# WCH_hairDrierCore_V1_5.net
KiCad netlist of a schematic drawn in Altium Designer
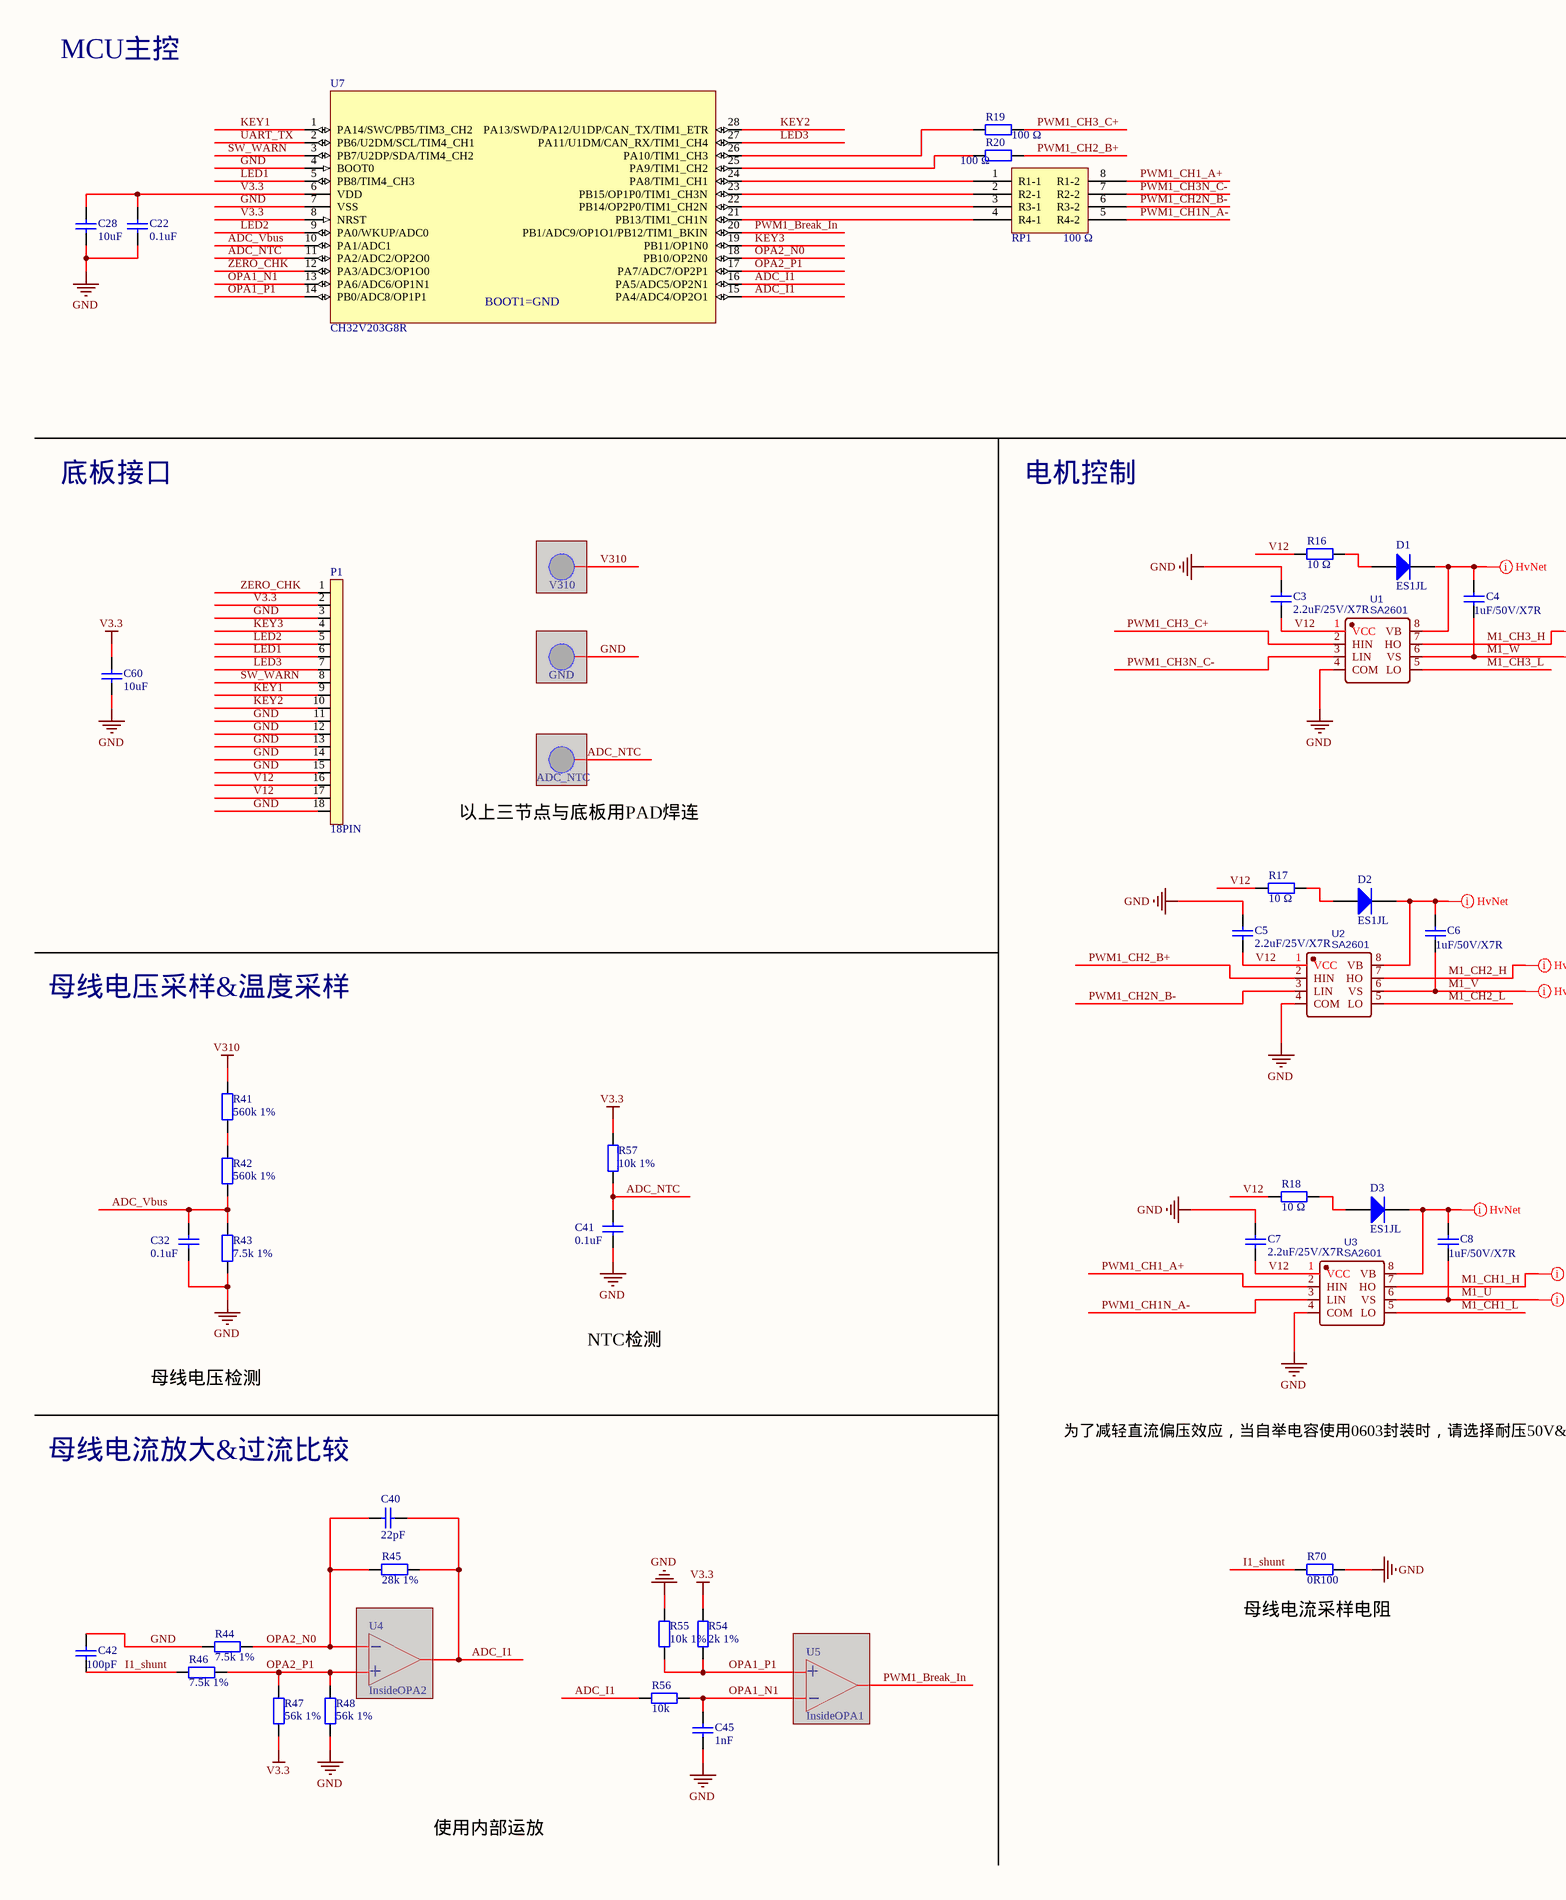
[diagram p0: WCH_hairDrierCore_V1.5.SchDoc, left]
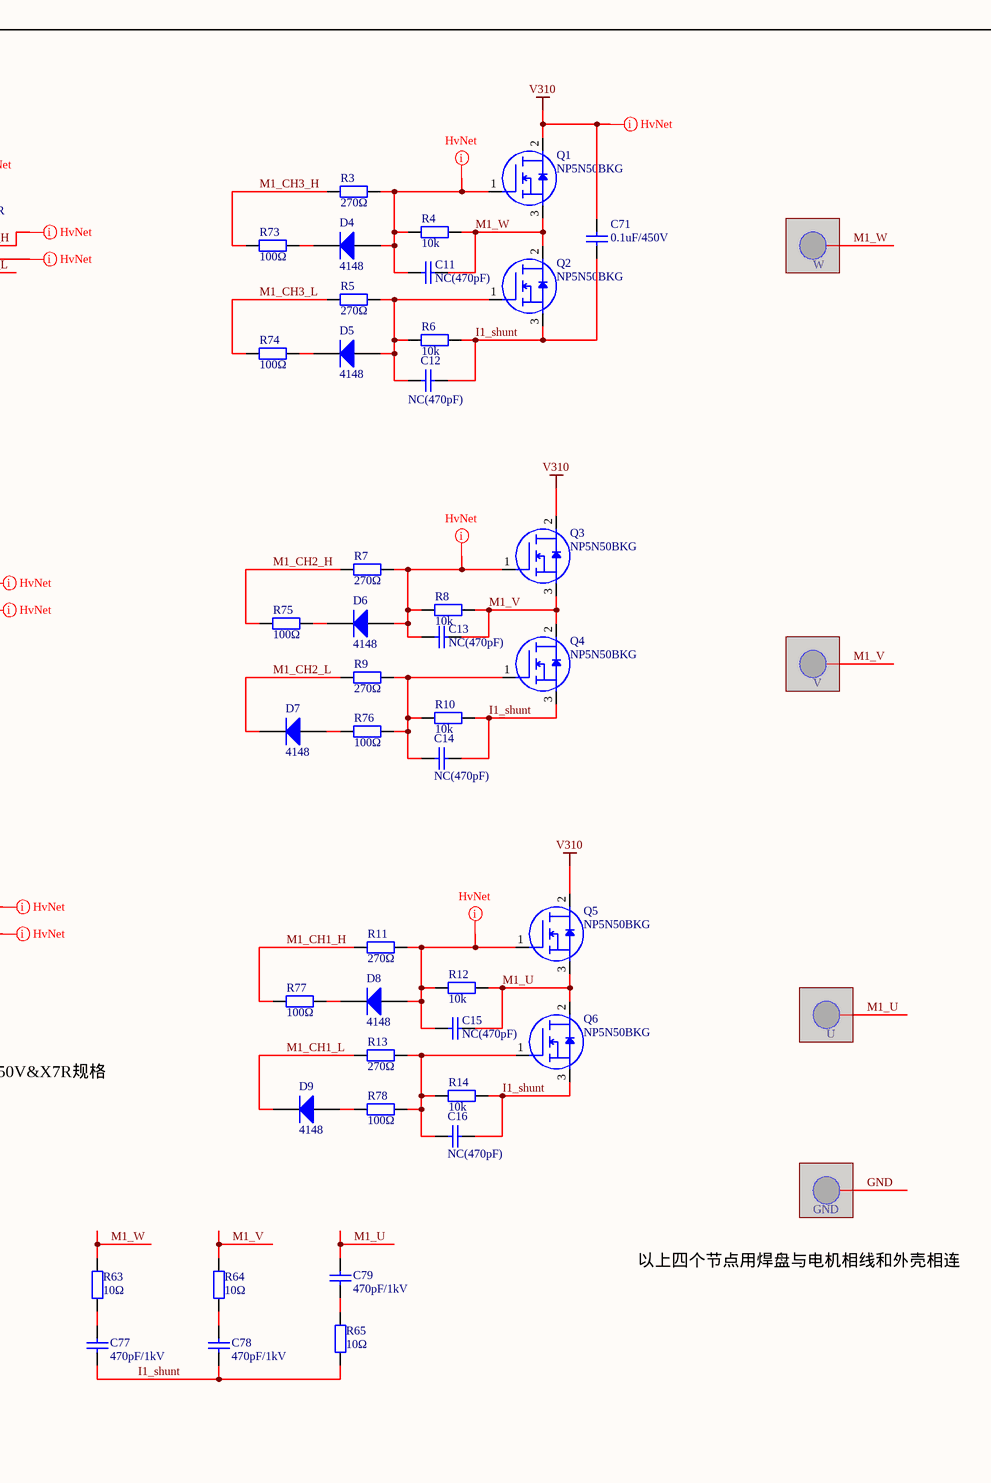
[diagram p1: WCH_hairDrierCore_V1.5.SchDoc, right]

(export (version "E")
  (design (tool "Eeschema 10.0.6"))
  (components
    (comp (ref "C3")
      (value "2.2uF/25V/X7R")
      (footprint "M_C0805")
      (description "Capacitor (Semiconductor SIM Model)")
      (fields (field (name "PUBLISHER") "Altium Limited"))
      (libsource (lib "Miscellaneous Devices") (part "Cap Semi"))
    )
    (comp (ref "C4")
      (value "1uF/50V/X7R")
      (footprint "M_C0805")
      (description "Capacitor (Semiconductor SIM Model)")
      (fields (field (name "PUBLISHER") "Altium Limited"))
      (libsource (lib "Miscellaneous Devices") (part "Cap Semi"))
    )
    (comp (ref "C5")
      (value "2.2uF/25V/X7R")
      (footprint "M_C0805")
      (description "Capacitor (Semiconductor SIM Model)")
      (fields (field (name "PUBLISHER") "Altium Limited"))
      (libsource (lib "Miscellaneous Devices") (part "Cap Semi"))
    )
    (comp (ref "C6")
      (value "1uF/50V/X7R")
      (footprint "M_C0805")
      (description "Capacitor (Semiconductor SIM Model)")
      (fields (field (name "PUBLISHER") "Altium Limited"))
      (libsource (lib "Miscellaneous Devices") (part "Cap Semi"))
    )
    (comp (ref "C7")
      (value "2.2uF/25V/X7R")
      (footprint "M_C0805")
      (description "Capacitor (Semiconductor SIM Model)")
      (fields (field (name "PUBLISHER") "Altium Limited"))
      (libsource (lib "Miscellaneous Devices") (part "Cap Semi"))
    )
    (comp (ref "C8")
      (value "1uF/50V/X7R")
      (footprint "M_C0805")
      (description "Capacitor (Semiconductor SIM Model)")
      (fields (field (name "PUBLISHER") "Altium Limited"))
      (libsource (lib "Miscellaneous Devices") (part "Cap Semi"))
    )
    (comp (ref "C11")
      (value "NC(470pF)")
      (footprint "M_C0402-")
      (description "Capacitor (Semiconductor SIM Model)")
      (fields (field (name "PUBLISHER") "Altium Limited"))
      (libsource (lib "Miscellaneous Devices") (part "Cap Semi"))
    )
    (comp (ref "C12")
      (value "NC(470pF)")
      (footprint "M_C0402-")
      (description "Capacitor (Semiconductor SIM Model)")
      (fields (field (name "PUBLISHER") "Altium Limited"))
      (libsource (lib "Miscellaneous Devices") (part "Cap Semi"))
    )
    (comp (ref "C13")
      (value "NC(470pF)")
      (footprint "M_C0402-")
      (description "Capacitor (Semiconductor SIM Model)")
      (fields (field (name "PUBLISHER") "Altium Limited"))
      (libsource (lib "Miscellaneous Devices") (part "Cap Semi"))
    )
    (comp (ref "C14")
      (value "NC(470pF)")
      (footprint "M_C0402-")
      (description "Capacitor (Semiconductor SIM Model)")
      (fields (field (name "PUBLISHER") "Altium Limited"))
      (libsource (lib "Miscellaneous Devices") (part "Cap Semi"))
    )
    (comp (ref "C15")
      (value "NC(470pF)")
      (footprint "M_C0402-")
      (description "Capacitor (Semiconductor SIM Model)")
      (fields (field (name "PUBLISHER") "Altium Limited"))
      (libsource (lib "Miscellaneous Devices") (part "Cap Semi"))
    )
    (comp (ref "C16")
      (value "NC(470pF)")
      (footprint "M_C0402-")
      (description "Capacitor (Semiconductor SIM Model)")
      (fields (field (name "PUBLISHER") "Altium Limited"))
      (libsource (lib "Miscellaneous Devices") (part "Cap Semi"))
    )
    (comp (ref "C22")
      (value "0.1uF")
      (footprint "C0402S")
      (description "Capacitor (Semiconductor SIM Model)")
      (fields (field (name "PUBLISHER") "Altium Limited"))
      (libsource (lib "Miscellaneous Devices") (part "Cap Semi"))
    )
    (comp (ref "C28")
      (value "10uF")
      (footprint "0603C")
      (description "Capacitor (Semiconductor SIM Model)")
      (fields (field (name "PUBLISHER") "Altium Limited"))
      (libsource (lib "Miscellaneous Devices") (part "Cap Semi"))
    )
    (comp (ref "C32")
      (value "0.1uF")
      (footprint "C0402S")
      (description "Capacitor (Semiconductor SIM Model)")
      (fields (field (name "PUBLISHER") "Altium Limited"))
      (libsource (lib "Miscellaneous Devices") (part "Cap Semi"))
    )
    (comp (ref "C40")
      (value "22pF")
      (footprint "C0402S")
      (description "Capacitor (Semiconductor SIM Model)")
      (fields (field (name "PUBLISHER") "Altium Limited"))
      (libsource (lib "Miscellaneous Devices") (part "Cap Semi"))
    )
    (comp (ref "C41")
      (value "0.1uF")
      (footprint "C0402S")
      (description "Capacitor (Semiconductor SIM Model)")
      (fields (field (name "PUBLISHER") "Altium Limited"))
      (libsource (lib "Miscellaneous Devices") (part "Cap Semi"))
    )
    (comp (ref "C42")
      (value "100pF")
      (footprint "C0402S")
      (description "Capacitor (Semiconductor SIM Model)")
      (fields (field (name "PUBLISHER") "Altium Limited"))
      (libsource (lib "Miscellaneous Devices") (part "Cap Semi"))
    )
    (comp (ref "C45")
      (value "1nF")
      (footprint "C0402S")
      (description "Capacitor (Semiconductor SIM Model)")
      (fields (field (name "PUBLISHER") "Altium Limited"))
      (libsource (lib "Miscellaneous Devices") (part "Cap Semi"))
    )
    (comp (ref "C60")
      (value "10uF")
      (footprint "0603C")
      (description "Capacitor (Semiconductor SIM Model)")
      (fields (field (name "PUBLISHER") "Altium Limited"))
      (libsource (lib "Miscellaneous Devices") (part "Cap Semi"))
    )
    (comp (ref "C71")
      (value "0.1uF/450V")
      (footprint "1206-")
      (description "Capacitor (Semiconductor SIM Model)")
      (fields (field (name "PUBLISHER") "Altium Limited"))
      (libsource (lib "Miscellaneous Devices") (part "Cap Semi"))
    )
    (comp (ref "C77")
      (value "470pF/1kV")
      (footprint "M_C1206-")
      (description "Capacitor (Semiconductor SIM Model)")
      (fields (field (name "PUBLISHER") "Altium Limited"))
      (libsource (lib "Miscellaneous Devices") (part "Cap Semi"))
    )
    (comp (ref "C78")
      (value "470pF/1kV")
      (footprint "M_C1206-")
      (description "Capacitor (Semiconductor SIM Model)")
      (fields (field (name "PUBLISHER") "Altium Limited"))
      (libsource (lib "Miscellaneous Devices") (part "Cap Semi"))
    )
    (comp (ref "C79")
      (value "470pF/1kV")
      (footprint "M_C1206-")
      (description "Capacitor (Semiconductor SIM Model)")
      (fields (field (name "PUBLISHER") "Altium Limited"))
      (libsource (lib "Miscellaneous Devices") (part "Cap Semi"))
    )
    (comp (ref "D1")
      (value "ES1JL")
      (footprint "SOD-123")
      (description "High Conductance Fast Diode")
      (fields (field (name "PUBLISHER") "Altium Limited"))
      (libsource (lib "Miscellaneous Devices") (part "Diode 1N4148"))
    )
    (comp (ref "D2")
      (value "ES1JL")
      (footprint "SOD-123")
      (description "High Conductance Fast Diode")
      (fields (field (name "PUBLISHER") "Altium Limited"))
      (libsource (lib "Miscellaneous Devices") (part "Diode 1N4148"))
    )
    (comp (ref "D3")
      (value "ES1JL")
      (footprint "SOD-123")
      (description "High Conductance Fast Diode")
      (fields (field (name "PUBLISHER") "Altium Limited"))
      (libsource (lib "Miscellaneous Devices") (part "Diode 1N4148"))
    )
    (comp (ref "D4")
      (value "4148")
      (footprint "SOD523")
      (description "High Conductance Fast Diode")
      (fields (field (name "PUBLISHER") "Altium Limited"))
      (libsource (lib "Miscellaneous Devices") (part "Diode 1N4148"))
    )
    (comp (ref "D5")
      (value "4148")
      (footprint "SOD523")
      (description "High Conductance Fast Diode")
      (fields (field (name "PUBLISHER") "Altium Limited"))
      (libsource (lib "Miscellaneous Devices") (part "Diode 1N4148"))
    )
    (comp (ref "D6")
      (value "4148")
      (footprint "SOD523")
      (description "High Conductance Fast Diode")
      (fields (field (name "PUBLISHER") "Altium Limited"))
      (libsource (lib "Miscellaneous Devices") (part "Diode 1N4148"))
    )
    (comp (ref "D7")
      (value "4148")
      (footprint "SOD523")
      (description "High Conductance Fast Diode")
      (fields (field (name "PUBLISHER") "Altium Limited"))
      (libsource (lib "Miscellaneous Devices") (part "Diode 1N4148"))
    )
    (comp (ref "D8")
      (value "4148")
      (footprint "SOD523")
      (description "High Conductance Fast Diode")
      (fields (field (name "PUBLISHER") "Altium Limited"))
      (libsource (lib "Miscellaneous Devices") (part "Diode 1N4148"))
    )
    (comp (ref "D9")
      (value "4148")
      (footprint "SOD523")
      (description "High Conductance Fast Diode")
      (fields (field (name "PUBLISHER") "Altium Limited"))
      (libsource (lib "Miscellaneous Devices") (part "Diode 1N4148"))
    )
    (comp (ref "P1") (value "18PIN") (footprint "P1.27-18-SMD") (libsource (lib "SUNWIN_SCH") (part "18PIN")))
    (comp (ref "Q1")
      (value "NP5N50BKG")
      (footprint "D-PAK-1")
      (libsource (lib "SUNWIN_SCH") (part "MOSFET-N"))
    )
    (comp (ref "Q2")
      (value "NP5N50BKG")
      (footprint "D-PAK-1")
      (libsource (lib "SUNWIN_SCH") (part "MOSFET-N"))
    )
    (comp (ref "Q3")
      (value "NP5N50BKG")
      (footprint "D-PAK-1")
      (libsource (lib "SUNWIN_SCH") (part "MOSFET-N"))
    )
    (comp (ref "Q4")
      (value "NP5N50BKG")
      (footprint "D-PAK-1")
      (libsource (lib "SUNWIN_SCH") (part "MOSFET-N"))
    )
    (comp (ref "Q5")
      (value "NP5N50BKG")
      (footprint "D-PAK-1")
      (libsource (lib "SUNWIN_SCH") (part "MOSFET-N"))
    )
    (comp (ref "Q6")
      (value "NP5N50BKG")
      (footprint "D-PAK-1")
      (libsource (lib "SUNWIN_SCH") (part "MOSFET-N"))
    )
    (comp (ref "R3")
      (value "270Ω")
      (footprint "M_R0402-")
      (description "Resistor")
      (fields (field (name "PUBLISHER") "Altium Limited"))
      (libsource (lib "") (part "Res2_1"))
    )
    (comp (ref "R4")
      (value "10k")
      (footprint "0402S")
      (description "Resistor")
      (fields (field (name "PUBLISHER") "Altium Limited"))
      (libsource (lib "") (part "Res2_1"))
    )
    (comp (ref "R5")
      (value "270Ω")
      (footprint "M_R0402-")
      (description "Resistor")
      (fields (field (name "PUBLISHER") "Altium Limited"))
      (libsource (lib "") (part "Res2_1"))
    )
    (comp (ref "R6")
      (value "10k")
      (footprint "0402S")
      (description "Resistor")
      (fields (field (name "PUBLISHER") "Altium Limited"))
      (libsource (lib "") (part "Res2_1"))
    )
    (comp (ref "R7")
      (value "270Ω")
      (footprint "M_R0402-")
      (description "Resistor")
      (fields (field (name "PUBLISHER") "Altium Limited"))
      (libsource (lib "") (part "Res2_1"))
    )
    (comp (ref "R8")
      (value "10k")
      (footprint "0402S")
      (description "Resistor")
      (fields (field (name "PUBLISHER") "Altium Limited"))
      (libsource (lib "") (part "Res2_1"))
    )
    (comp (ref "R9")
      (value "270Ω")
      (footprint "M_R0402-")
      (description "Resistor")
      (fields (field (name "PUBLISHER") "Altium Limited"))
      (libsource (lib "") (part "Res2_1"))
    )
    (comp (ref "R10")
      (value "10k")
      (footprint "0402S")
      (description "Resistor")
      (fields (field (name "PUBLISHER") "Altium Limited"))
      (libsource (lib "") (part "Res2_1"))
    )
    (comp (ref "R11")
      (value "270Ω")
      (footprint "M_R0402-")
      (description "Resistor")
      (fields (field (name "PUBLISHER") "Altium Limited"))
      (libsource (lib "") (part "Res2_1"))
    )
    (comp (ref "R12")
      (value "10k")
      (footprint "0402S")
      (description "Resistor")
      (fields (field (name "PUBLISHER") "Altium Limited"))
      (libsource (lib "") (part "Res2_1"))
    )
    (comp (ref "R13")
      (value "270Ω")
      (footprint "M_R0402-")
      (description "Resistor")
      (fields (field (name "PUBLISHER") "Altium Limited"))
      (libsource (lib "") (part "Res2_1"))
    )
    (comp (ref "R14")
      (value "10k")
      (footprint "0402S")
      (description "Resistor")
      (fields (field (name "PUBLISHER") "Altium Limited"))
      (libsource (lib "") (part "Res2_1"))
    )
    (comp (ref "R16")
      (value "10 Ω")
      (footprint "0603")
      (description "Resistor")
      (fields (field (name "PUBLISHER") "Altium Limited"))
      (libsource (lib "") (part "Res2_1"))
    )
    (comp (ref "R17")
      (value "10 Ω")
      (footprint "0603")
      (description "Resistor")
      (fields (field (name "PUBLISHER") "Altium Limited"))
      (libsource (lib "") (part "Res2_1"))
    )
    (comp (ref "R18")
      (value "10 Ω")
      (footprint "0603")
      (description "Resistor")
      (fields (field (name "PUBLISHER") "Altium Limited"))
      (libsource (lib "") (part "Res2_1"))
    )
    (comp (ref "R19")
      (value "100 Ω")
      (footprint "C0402S")
      (description "Resistor")
      (fields (field (name "PUBLISHER") "Altium Limited"))
      (libsource (lib "") (part "Res2_1"))
    )
    (comp (ref "R20")
      (value "100 Ω")
      (footprint "C0402S")
      (description "Resistor")
      (fields (field (name "PUBLISHER") "Altium Limited"))
      (libsource (lib "") (part "Res2_1"))
    )
    (comp (ref "R41")
      (value "560k 1%")
      (footprint "1206-")
      (description "Resistor")
      (fields (field (name "PUBLISHER") "Altium Limited"))
      (libsource (lib "Miscellaneous Devices") (part "Res2"))
    )
    (comp (ref "R42")
      (value "560k 1%")
      (footprint "1206-")
      (description "Resistor")
      (fields (field (name "PUBLISHER") "Altium Limited"))
      (libsource (lib "Miscellaneous Devices") (part "Res2"))
    )
    (comp (ref "R43")
      (value "7.5k 1%")
      (footprint "0402S")
      (description "Resistor")
      (fields (field (name "PUBLISHER") "Altium Limited"))
      (libsource (lib "Miscellaneous Devices") (part "Res2"))
    )
    (comp (ref "R44")
      (value "7.5k 1%")
      (footprint "0402S")
      (description "Resistor")
      (fields (field (name "PUBLISHER") "Altium Limited"))
      (libsource (lib "") (part "Res2_2"))
    )
    (comp (ref "R45")
      (value "28k 1%")
      (footprint "0402S")
      (description "Resistor")
      (fields (field (name "PUBLISHER") "Altium Limited"))
      (libsource (lib "") (part "Res2_2"))
    )
    (comp (ref "R46")
      (value "7.5k 1%")
      (footprint "0402S")
      (description "Resistor")
      (fields (field (name "PUBLISHER") "Altium Limited"))
      (libsource (lib "") (part "Res2_2"))
    )
    (comp (ref "R47")
      (value "56k 1%")
      (footprint "0402S")
      (description "Resistor")
      (fields (field (name "PUBLISHER") "Altium Limited"))
      (libsource (lib "Miscellaneous Devices") (part "Res2"))
    )
    (comp (ref "R48")
      (value "56k 1%")
      (footprint "0402S")
      (description "Resistor")
      (fields (field (name "PUBLISHER") "Altium Limited"))
      (libsource (lib "Miscellaneous Devices") (part "Res2"))
    )
    (comp (ref "R54")
      (value "2k 1%")
      (footprint "0402S")
      (description "Resistor")
      (fields (field (name "PUBLISHER") "Altium Limited"))
      (libsource (lib "") (part "Res2_3"))
    )
    (comp (ref "R55")
      (value "10k 1%")
      (footprint "0402S")
      (description "Resistor")
      (fields (field (name "PUBLISHER") "Altium Limited"))
      (libsource (lib "Miscellaneous Devices") (part "Res2"))
    )
    (comp (ref "R56")
      (value "10k")
      (footprint "0402S")
      (description "Resistor")
      (fields (field (name "PUBLISHER") "Altium Limited"))
      (libsource (lib "") (part "Res2_2"))
    )
    (comp (ref "R57")
      (value "10k 1%")
      (footprint "0402S")
      (description "Resistor")
      (fields (field (name "PUBLISHER") "Altium Limited"))
      (libsource (lib "") (part "Res2_3"))
    )
    (comp (ref "R63")
      (value "10Ω")
      (footprint "M_R0805-")
      (description "Resistor")
      (fields (field (name "PUBLISHER") "Altium Limited"))
      (libsource (lib "Miscellaneous Devices") (part "Res2"))
    )
    (comp (ref "R64")
      (value "10Ω")
      (footprint "M_R0805-")
      (description "Resistor")
      (fields (field (name "PUBLISHER") "Altium Limited"))
      (libsource (lib "Miscellaneous Devices") (part "Res2"))
    )
    (comp (ref "R65")
      (value "10Ω")
      (footprint "M_R0805-")
      (description "Resistor")
      (fields (field (name "PUBLISHER") "Altium Limited"))
      (libsource (lib "Miscellaneous Devices") (part "Res2"))
    )
    (comp (ref "R70")
      (value "0R100")
      (footprint "1210")
      (description "Resistor")
      (fields (field (name "PUBLISHER") "Altium Limited"))
      (libsource (lib "") (part "Res2_1"))
    )
    (comp (ref "R73")
      (value "100Ω")
      (footprint "M_R0402-")
      (description "Resistor")
      (fields (field (name "PUBLISHER") "Altium Limited"))
      (libsource (lib "") (part "Res2_1"))
    )
    (comp (ref "R74")
      (value "100Ω")
      (footprint "M_R0402-")
      (description "Resistor")
      (fields (field (name "PUBLISHER") "Altium Limited"))
      (libsource (lib "") (part "Res2_1"))
    )
    (comp (ref "R75")
      (value "100Ω")
      (footprint "M_R0402-")
      (description "Resistor")
      (fields (field (name "PUBLISHER") "Altium Limited"))
      (libsource (lib "") (part "Res2_1"))
    )
    (comp (ref "R76")
      (value "100Ω")
      (footprint "M_R0402-")
      (description "Resistor")
      (fields (field (name "PUBLISHER") "Altium Limited"))
      (libsource (lib "") (part "Res2_1"))
    )
    (comp (ref "R77")
      (value "100Ω")
      (footprint "M_R0402-")
      (description "Resistor")
      (fields (field (name "PUBLISHER") "Altium Limited"))
      (libsource (lib "") (part "Res2_1"))
    )
    (comp (ref "R78")
      (value "100Ω")
      (footprint "M_R0402-")
      (description "Resistor")
      (fields (field (name "PUBLISHER") "Altium Limited"))
      (libsource (lib "") (part "Res2_1"))
    )
    (comp (ref "RP1") (value "100 Ω") (footprint "RP4-0402") (libsource (lib "WJ1") (part "Rp4")))
    (comp (ref "U1")
      (value "SA2601")
      (footprint "SOP8")
      (fields
        (field (name "BOM_SUPPLIER PART") "C537541")
        (field (name "BOM_MANUFACTURER PART") "IR2101SPBF")
        (field (name "CONTRIBUTOR") "LCSC")
      )
      (libsource (lib "altium-import") (part "root_0_IR2101SPBF_"))
    )
    (comp (ref "U2")
      (value "SA2601")
      (footprint "SOP8")
      (fields
        (field (name "BOM_SUPPLIER PART") "C537541")
        (field (name "BOM_MANUFACTURER PART") "IR2101SPBF")
        (field (name "CONTRIBUTOR") "LCSC")
      )
      (libsource (lib "altium-import") (part "root_0_IR2101SPBF_"))
    )
    (comp (ref "U3")
      (value "SA2601")
      (footprint "SOP8")
      (fields
        (field (name "BOM_SUPPLIER PART") "C537541")
        (field (name "BOM_MANUFACTURER PART") "IR2101SPBF")
        (field (name "CONTRIBUTOR") "LCSC")
      )
      (libsource (lib "altium-import") (part "root_0_IR2101SPBF_"))
    )
    (comp (ref "U4") (value "InsideOPA2") (libsource (lib "WJ1") (part "InsideOPA")))
    (comp (ref "U5") (value "InsideOPA1") (libsource (lib "WJ1") (part "InsideOPA2")))
    (comp (ref "U7")
      (value "CH32V203G8R")
      (footprint "QSOP28")
      (description "RISC-V LMD-MCU, 144MHz, for motor & wireless charging")
      (libsource (lib "CHXXX") (part "CH32V203G8R"))
    )
  )
  (nets
    (net (code "1") (name "/ADC_I1") (class "Default")
      (node (ref "C40") (pin "1") (pinfunction "1_1") (pintype "passive"))
      (node (ref "R45") (pin "2") (pinfunction "2_2") (pintype "passive"))
      (node (ref "R56") (pin "1") (pinfunction "1_1") (pintype "passive"))
      (node (ref "U7") (pin "15") (pinfunction "PA4/ADC4/OP2O1_15") (pintype "bidirectional"))
      (node (ref "U7") (pin "16") (pinfunction "PA5/ADC5/OP2N1_16") (pintype "bidirectional"))
    )
    (net (code "2") (name "/ADC_NTC") (class "Default")
      (node (ref "C41") (pin "1") (pinfunction "1_1") (pintype "passive"))
      (node (ref "R57") (pin "2") (pinfunction "2_2") (pintype "passive"))
      (node (ref "U7") (pin "11") (pinfunction "PA2/ADC2/OP2O0_11") (pintype "bidirectional"))
    )
    (net (code "3") (name "/ADC_Vbus") (class "Default")
      (node (ref "C32") (pin "1") (pinfunction "1_1") (pintype "passive"))
      (node (ref "R42") (pin "1") (pinfunction "1_1") (pintype "passive"))
      (node (ref "R43") (pin "2") (pinfunction "2_2") (pintype "passive"))
      (node (ref "U7") (pin "10") (pinfunction "PA1/ADC1_10") (pintype "bidirectional"))
    )
    (net (code "4") (name "/I1_shunt") (class "Default")
      (node (ref "C12") (pin "2") (pinfunction "2_2") (pintype "passive"))
      (node (ref "C14") (pin "2") (pinfunction "2_2") (pintype "passive"))
      (node (ref "C16") (pin "2") (pinfunction "2_2") (pintype "passive"))
      (node (ref "C42") (pin "2") (pinfunction "2_2") (pintype "passive"))
      (node (ref "C71") (pin "2") (pinfunction "2_2") (pintype "passive"))
      (node (ref "C77") (pin "1") (pinfunction "1_1") (pintype "passive"))
      (node (ref "C78") (pin "1") (pinfunction "1_1") (pintype "passive"))
      (node (ref "Q2") (pin "3") (pinfunction "S_3") (pintype "passive"))
      (node (ref "Q4") (pin "3") (pinfunction "S_3") (pintype "passive"))
      (node (ref "Q6") (pin "3") (pinfunction "S_3") (pintype "passive"))
      (node (ref "R10") (pin "1") (pinfunction "1_1") (pintype "passive"))
      (node (ref "R14") (pin "1") (pinfunction "1_1") (pintype "passive"))
      (node (ref "R46") (pin "1") (pinfunction "1_1") (pintype "passive"))
      (node (ref "R6") (pin "1") (pinfunction "1_1") (pintype "passive"))
      (node (ref "R65") (pin "1") (pinfunction "1_1") (pintype "passive"))
      (node (ref "R70") (pin "2") (pinfunction "2_2") (pintype "passive"))
    )
    (net (code "5") (name "/KEY1") (class "Default")
      (node (ref "P1") (pin "9") (pintype "passive"))
      (node (ref "U7") (pin "1") (pinfunction "PA14/SWC/PB5/TIM3_CH2_1") (pintype "bidirectional"))
    )
    (net (code "6") (name "/KEY2") (class "Default")
      (node (ref "P1") (pin "10") (pintype "passive"))
      (node (ref "U7") (pin "28") (pinfunction "PA13/SWD/PA12/U1DP/CAN_TX/TIM1_ETR_28") (pintype "bidirectional"))
    )
    (net (code "7") (name "/KEY3") (class "Default")
      (node (ref "P1") (pin "4") (pintype "passive"))
      (node (ref "U7") (pin "19") (pinfunction "PB11/OP1N0_19") (pintype "bidirectional"))
    )
    (net (code "8") (name "/LED1") (class "Default")
      (node (ref "P1") (pin "6") (pintype "passive"))
      (node (ref "U7") (pin "5") (pinfunction "PB8/TIM4_CH3_5") (pintype "bidirectional"))
    )
    (net (code "9") (name "/LED2") (class "Default")
      (node (ref "P1") (pin "5") (pintype "passive"))
      (node (ref "U7") (pin "9") (pinfunction "PA0/WKUP/ADC0_9") (pintype "bidirectional"))
    )
    (net (code "10") (name "/LED3") (class "Default")
      (node (ref "P1") (pin "7") (pintype "passive"))
      (node (ref "U7") (pin "27") (pinfunction "PA11/U1DM/CAN_RX/TIM1_CH4_27") (pintype "bidirectional"))
    )
    (net (code "11") (name "/M1_CH1_H") (class "Default")
      (node (ref "R11") (pin "2") (pinfunction "2_2") (pintype "passive"))
      (node (ref "R77") (pin "2") (pinfunction "2_2") (pintype "passive"))
      (node (ref "U3") (pin "7") (pinfunction "HO_7") (pintype "passive"))
    )
    (net (code "12") (name "/M1_CH1_L") (class "Default")
      (node (ref "D9") (pin "2") (pinfunction "K_2") (pintype "passive"))
      (node (ref "R13") (pin "2") (pinfunction "2_2") (pintype "passive"))
      (node (ref "U3") (pin "5") (pinfunction "LO_5") (pintype "passive"))
    )
    (net (code "13") (name "/M1_CH2_H") (class "Default")
      (node (ref "R7") (pin "2") (pinfunction "2_2") (pintype "passive"))
      (node (ref "R75") (pin "2") (pinfunction "2_2") (pintype "passive"))
      (node (ref "U2") (pin "7") (pinfunction "HO_7") (pintype "passive"))
    )
    (net (code "14") (name "/M1_CH2_L") (class "Default")
      (node (ref "D7") (pin "2") (pinfunction "K_2") (pintype "passive"))
      (node (ref "R9") (pin "2") (pinfunction "2_2") (pintype "passive"))
      (node (ref "U2") (pin "5") (pinfunction "LO_5") (pintype "passive"))
    )
    (net (code "15") (name "/M1_CH3_H") (class "Default")
      (node (ref "R3") (pin "2") (pinfunction "2_2") (pintype "passive"))
      (node (ref "R73") (pin "2") (pinfunction "2_2") (pintype "passive"))
      (node (ref "U1") (pin "7") (pinfunction "HO_7") (pintype "passive"))
    )
    (net (code "16") (name "/M1_CH3_L") (class "Default")
      (node (ref "R5") (pin "2") (pinfunction "2_2") (pintype "passive"))
      (node (ref "R74") (pin "2") (pinfunction "2_2") (pintype "passive"))
      (node (ref "U1") (pin "5") (pinfunction "LO_5") (pintype "passive"))
    )
    (net (code "17") (name "/M1_U") (class "Default")
      (node (ref "C15") (pin "2") (pinfunction "2_2") (pintype "passive"))
      (node (ref "C79") (pin "2") (pinfunction "2_2") (pintype "passive"))
      (node (ref "C8") (pin "2") (pinfunction "2_2") (pintype "passive"))
      (node (ref "Q5") (pin "3") (pinfunction "S_3") (pintype "passive"))
      (node (ref "Q6") (pin "2") (pinfunction "D_2") (pintype "passive"))
      (node (ref "R12") (pin "1") (pinfunction "1_1") (pintype "passive"))
      (node (ref "U3") (pin "6") (pinfunction "VS_6") (pintype "passive"))
    )
    (net (code "18") (name "/M1_V") (class "Default")
      (node (ref "C13") (pin "2") (pinfunction "2_2") (pintype "passive"))
      (node (ref "C6") (pin "2") (pinfunction "2_2") (pintype "passive"))
      (node (ref "Q3") (pin "3") (pinfunction "S_3") (pintype "passive"))
      (node (ref "Q4") (pin "2") (pinfunction "D_2") (pintype "passive"))
      (node (ref "R64") (pin "2") (pinfunction "2_2") (pintype "passive"))
      (node (ref "R8") (pin "1") (pinfunction "1_1") (pintype "passive"))
      (node (ref "U2") (pin "6") (pinfunction "VS_6") (pintype "passive"))
    )
    (net (code "19") (name "/M1_W") (class "Default")
      (node (ref "C11") (pin "2") (pinfunction "2_2") (pintype "passive"))
      (node (ref "C4") (pin "2") (pinfunction "2_2") (pintype "passive"))
      (node (ref "Q1") (pin "3") (pinfunction "S_3") (pintype "passive"))
      (node (ref "Q2") (pin "2") (pinfunction "D_2") (pintype "passive"))
      (node (ref "R4") (pin "1") (pinfunction "1_1") (pintype "passive"))
      (node (ref "R63") (pin "2") (pinfunction "2_2") (pintype "passive"))
      (node (ref "U1") (pin "6") (pinfunction "VS_6") (pintype "passive"))
    )
    (net (code "20") (name "/OPA1_N1") (class "Default")
      (node (ref "C45") (pin "2") (pinfunction "2_2") (pintype "passive"))
      (node (ref "R56") (pin "2") (pinfunction "2_2") (pintype "passive"))
      (node (ref "U7") (pin "13") (pinfunction "PA6/ADC6/OP1N1_13") (pintype "bidirectional"))
    )
    (net (code "21") (name "/OPA1_P1") (class "Default")
      (node (ref "R54") (pin "2") (pinfunction "2_2") (pintype "passive"))
      (node (ref "R55") (pin "1") (pinfunction "1_1") (pintype "passive"))
      (node (ref "U7") (pin "14") (pinfunction "PB0/ADC8/OP1P1_14") (pintype "bidirectional"))
    )
    (net (code "22") (name "/OPA2_N0") (class "Default")
      (node (ref "C40") (pin "2") (pinfunction "2_2") (pintype "passive"))
      (node (ref "R44") (pin "2") (pinfunction "2_2") (pintype "passive"))
      (node (ref "R45") (pin "1") (pinfunction "1_1") (pintype "passive"))
      (node (ref "U7") (pin "18") (pinfunction "PB10/OP2N0_18") (pintype "bidirectional"))
    )
    (net (code "23") (name "/OPA2_P1") (class "Default")
      (node (ref "R46") (pin "2") (pinfunction "2_2") (pintype "passive"))
      (node (ref "R47") (pin "2") (pinfunction "2_2") (pintype "passive"))
      (node (ref "R48") (pin "2") (pinfunction "2_2") (pintype "passive"))
      (node (ref "U7") (pin "17") (pinfunction "PA7/ADC7/OP2P1_17") (pintype "bidirectional"))
    )
    (net (code "24") (name "/PWM1_Break_In") (class "Default")
      (node (ref "U7") (pin "20") (pinfunction "PB1/ADC9/OP1O1/PB12/TIM1_BKIN_20") (pintype "bidirectional"))
    )
    (net (code "25") (name "/PWM1_CH1N_A-") (class "Default")
      (node (ref "RP1") (pin "5") (pinfunction "R4-2_5") (pintype "passive"))
      (node (ref "U3") (pin "3") (pinfunction "LIN_3") (pintype "passive"))
    )
    (net (code "26") (name "/PWM1_CH1_A+") (class "Default")
      (node (ref "RP1") (pin "8") (pinfunction "R1-2_8") (pintype "passive"))
      (node (ref "U3") (pin "2") (pinfunction "HIN_2") (pintype "passive"))
    )
    (net (code "27") (name "/PWM1_CH2N_B-") (class "Default")
      (node (ref "RP1") (pin "6") (pinfunction "R3-2_6") (pintype "passive"))
      (node (ref "U2") (pin "3") (pinfunction "LIN_3") (pintype "passive"))
    )
    (net (code "28") (name "/PWM1_CH2_B+") (class "Default")
      (node (ref "R20") (pin "1") (pinfunction "1_1") (pintype "passive"))
      (node (ref "U2") (pin "2") (pinfunction "HIN_2") (pintype "passive"))
    )
    (net (code "29") (name "/PWM1_CH3N_C-") (class "Default")
      (node (ref "RP1") (pin "7") (pinfunction "R2-2_7") (pintype "passive"))
      (node (ref "U1") (pin "3") (pinfunction "LIN_3") (pintype "passive"))
    )
    (net (code "30") (name "/PWM1_CH3_C+") (class "Default")
      (node (ref "R19") (pin "1") (pinfunction "1_1") (pintype "passive"))
      (node (ref "U1") (pin "2") (pinfunction "HIN_2") (pintype "passive"))
    )
    (net (code "31") (name "/SW_WARN") (class "Default")
      (node (ref "P1") (pin "8") (pintype "passive"))
      (node (ref "U7") (pin "3") (pinfunction "PB7/U2DP/SDA/TIM4_CH2_3") (pintype "bidirectional"))
    )
    (net (code "32") (name "/UART_TX") (class "Default")
      (node (ref "U7") (pin "2") (pinfunction "PB6/U2DM/SCL/TIM4_CH1_2") (pintype "bidirectional"))
    )
    (net (code "33") (name "/V12") (class "Default")
      (node (ref "C3") (pin "1") (pinfunction "1_1") (pintype "passive"))
      (node (ref "C5") (pin "1") (pinfunction "1_1") (pintype "passive"))
      (node (ref "C7") (pin "1") (pinfunction "1_1") (pintype "passive"))
      (node (ref "P1") (pin "16") (pintype "passive"))
      (node (ref "P1") (pin "17") (pintype "passive"))
      (node (ref "R16") (pin "2") (pinfunction "2_2") (pintype "passive"))
      (node (ref "R17") (pin "2") (pinfunction "2_2") (pintype "passive"))
      (node (ref "R18") (pin "2") (pinfunction "2_2") (pintype "passive"))
      (node (ref "U1") (pin "1") (pinfunction "VCC_1") (pintype "passive"))
      (node (ref "U2") (pin "1") (pinfunction "VCC_1") (pintype "passive"))
      (node (ref "U3") (pin "1") (pinfunction "VCC_1") (pintype "passive"))
    )
    (net (code "34") (name "/ZERO_CHK") (class "Default")
      (node (ref "P1") (pin "1") (pintype "passive"))
      (node (ref "U7") (pin "12") (pinfunction "PA3/ADC3/OP1O0_12") (pintype "bidirectional"))
    )
    (net (code "35") (name "GND") (class "Default")
      (node (ref "C22") (pin "2") (pinfunction "2_2") (pintype "passive"))
      (node (ref "C28") (pin "2") (pinfunction "2_2") (pintype "passive"))
      (node (ref "C3") (pin "2") (pinfunction "2_2") (pintype "passive"))
      (node (ref "C32") (pin "2") (pinfunction "2_2") (pintype "passive"))
      (node (ref "C41") (pin "2") (pinfunction "2_2") (pintype "passive"))
      (node (ref "C42") (pin "1") (pinfunction "1_1") (pintype "passive"))
      (node (ref "C45") (pin "1") (pinfunction "1_1") (pintype "passive"))
      (node (ref "C5") (pin "2") (pinfunction "2_2") (pintype "passive"))
      (node (ref "C60") (pin "2") (pinfunction "2_2") (pintype "passive"))
      (node (ref "C7") (pin "2") (pinfunction "2_2") (pintype "passive"))
      (node (ref "P1") (pin "11") (pintype "passive"))
      (node (ref "P1") (pin "12") (pintype "passive"))
      (node (ref "P1") (pin "13") (pintype "passive"))
      (node (ref "P1") (pin "14") (pintype "passive"))
      (node (ref "P1") (pin "15") (pintype "passive"))
      (node (ref "P1") (pin "18") (pintype "passive"))
      (node (ref "P1") (pin "3") (pintype "passive"))
      (node (ref "R43") (pin "1") (pinfunction "1_1") (pintype "passive"))
      (node (ref "R44") (pin "1") (pinfunction "1_1") (pintype "passive"))
      (node (ref "R48") (pin "1") (pinfunction "1_1") (pintype "passive"))
      (node (ref "R55") (pin "2") (pinfunction "2_2") (pintype "passive"))
      (node (ref "R70") (pin "1") (pinfunction "1_1") (pintype "passive"))
      (node (ref "U1") (pin "4") (pinfunction "COM_4") (pintype "passive"))
      (node (ref "U2") (pin "4") (pinfunction "COM_4") (pintype "passive"))
      (node (ref "U3") (pin "4") (pinfunction "COM_4") (pintype "passive"))
      (node (ref "U7") (pin "4") (pinfunction "BOOT0_4") (pintype "input"))
      (node (ref "U7") (pin "7") (pinfunction "VSS_7") (pintype "power_in"))
    )
    (net (code "36") (name "Net-(C77-Pad2)") (class "Default")
      (node (ref "C77") (pin "2") (pinfunction "2_2") (pintype "passive"))
      (node (ref "R63") (pin "1") (pinfunction "1_1") (pintype "passive"))
    )
    (net (code "37") (name "Net-(C78-Pad2)") (class "Default")
      (node (ref "C78") (pin "2") (pinfunction "2_2") (pintype "passive"))
      (node (ref "R64") (pin "1") (pinfunction "1_1") (pintype "passive"))
    )
    (net (code "38") (name "Net-(C79-Pad1)") (class "Default")
      (node (ref "C79") (pin "1") (pinfunction "1_1") (pintype "passive"))
      (node (ref "R65") (pin "2") (pinfunction "2_2") (pintype "passive"))
    )
    (net (code "39") (name "Net-(D1-A)") (class "Default")
      (node (ref "D1") (pin "1") (pinfunction "A_1") (pintype "passive"))
      (node (ref "R16") (pin "1") (pinfunction "1_1") (pintype "passive"))
    )
    (net (code "40") (name "Net-(D1-K)") (class "Default")
      (node (ref "C4") (pin "1") (pinfunction "1_1") (pintype "passive"))
      (node (ref "D1") (pin "2") (pinfunction "K_2") (pintype "passive"))
      (node (ref "U1") (pin "8") (pinfunction "VB_8") (pintype "passive"))
    )
    (net (code "41") (name "Net-(D2-A)") (class "Default")
      (node (ref "D2") (pin "1") (pinfunction "A_1") (pintype "passive"))
      (node (ref "R17") (pin "1") (pinfunction "1_1") (pintype "passive"))
    )
    (net (code "42") (name "Net-(D2-K)") (class "Default")
      (node (ref "C6") (pin "1") (pinfunction "1_1") (pintype "passive"))
      (node (ref "D2") (pin "2") (pinfunction "K_2") (pintype "passive"))
      (node (ref "U2") (pin "8") (pinfunction "VB_8") (pintype "passive"))
    )
    (net (code "43") (name "Net-(D3-A)") (class "Default")
      (node (ref "D3") (pin "1") (pinfunction "A_1") (pintype "passive"))
      (node (ref "R18") (pin "1") (pinfunction "1_1") (pintype "passive"))
    )
    (net (code "44") (name "Net-(D3-K)") (class "Default")
      (node (ref "C8") (pin "1") (pinfunction "1_1") (pintype "passive"))
      (node (ref "D3") (pin "2") (pinfunction "K_2") (pintype "passive"))
      (node (ref "U3") (pin "8") (pinfunction "VB_8") (pintype "passive"))
    )
    (net (code "45") (name "Net-(D4-A)") (class "Default")
      (node (ref "C11") (pin "1") (pinfunction "1_1") (pintype "passive"))
      (node (ref "D4") (pin "1") (pinfunction "A_1") (pintype "passive"))
      (node (ref "Q1") (pin "1") (pinfunction "G_1") (pintype "passive"))
      (node (ref "R3") (pin "1") (pinfunction "1_1") (pintype "passive"))
      (node (ref "R4") (pin "2") (pinfunction "2_2") (pintype "passive"))
    )
    (net (code "46") (name "Net-(D4-K)") (class "Default")
      (node (ref "D4") (pin "2") (pinfunction "K_2") (pintype "passive"))
      (node (ref "R73") (pin "1") (pinfunction "1_1") (pintype "passive"))
    )
    (net (code "47") (name "Net-(D5-A)") (class "Default")
      (node (ref "C12") (pin "1") (pinfunction "1_1") (pintype "passive"))
      (node (ref "D5") (pin "1") (pinfunction "A_1") (pintype "passive"))
      (node (ref "Q2") (pin "1") (pinfunction "G_1") (pintype "passive"))
      (node (ref "R5") (pin "1") (pinfunction "1_1") (pintype "passive"))
      (node (ref "R6") (pin "2") (pinfunction "2_2") (pintype "passive"))
    )
    (net (code "48") (name "Net-(D5-K)") (class "Default")
      (node (ref "D5") (pin "2") (pinfunction "K_2") (pintype "passive"))
      (node (ref "R74") (pin "1") (pinfunction "1_1") (pintype "passive"))
    )
    (net (code "49") (name "Net-(D6-A)") (class "Default")
      (node (ref "C13") (pin "1") (pinfunction "1_1") (pintype "passive"))
      (node (ref "D6") (pin "1") (pinfunction "A_1") (pintype "passive"))
      (node (ref "Q3") (pin "1") (pinfunction "G_1") (pintype "passive"))
      (node (ref "R7") (pin "1") (pinfunction "1_1") (pintype "passive"))
      (node (ref "R8") (pin "2") (pinfunction "2_2") (pintype "passive"))
    )
    (net (code "50") (name "Net-(D6-K)") (class "Default")
      (node (ref "D6") (pin "2") (pinfunction "K_2") (pintype "passive"))
      (node (ref "R75") (pin "1") (pinfunction "1_1") (pintype "passive"))
    )
    (net (code "51") (name "Net-(D7-A)") (class "Default")
      (node (ref "D7") (pin "1") (pinfunction "A_1") (pintype "passive"))
      (node (ref "R76") (pin "2") (pinfunction "2_2") (pintype "passive"))
    )
    (net (code "52") (name "Net-(D8-A)") (class "Default")
      (node (ref "C15") (pin "1") (pinfunction "1_1") (pintype "passive"))
      (node (ref "D8") (pin "1") (pinfunction "A_1") (pintype "passive"))
      (node (ref "Q5") (pin "1") (pinfunction "G_1") (pintype "passive"))
      (node (ref "R11") (pin "1") (pinfunction "1_1") (pintype "passive"))
      (node (ref "R12") (pin "2") (pinfunction "2_2") (pintype "passive"))
    )
    (net (code "53") (name "Net-(D8-K)") (class "Default")
      (node (ref "D8") (pin "2") (pinfunction "K_2") (pintype "passive"))
      (node (ref "R77") (pin "1") (pinfunction "1_1") (pintype "passive"))
    )
    (net (code "54") (name "Net-(D9-A)") (class "Default")
      (node (ref "D9") (pin "1") (pinfunction "A_1") (pintype "passive"))
      (node (ref "R78") (pin "2") (pinfunction "2_2") (pintype "passive"))
    )
    (net (code "55") (name "Net-(Q4-G)") (class "Default")
      (node (ref "C14") (pin "1") (pinfunction "1_1") (pintype "passive"))
      (node (ref "Q4") (pin "1") (pinfunction "G_1") (pintype "passive"))
      (node (ref "R10") (pin "2") (pinfunction "2_2") (pintype "passive"))
      (node (ref "R76") (pin "1") (pinfunction "1_1") (pintype "passive"))
      (node (ref "R9") (pin "1") (pinfunction "1_1") (pintype "passive"))
    )
    (net (code "56") (name "Net-(Q6-G)") (class "Default")
      (node (ref "C16") (pin "1") (pinfunction "1_1") (pintype "passive"))
      (node (ref "Q6") (pin "1") (pinfunction "G_1") (pintype "passive"))
      (node (ref "R13") (pin "1") (pinfunction "1_1") (pintype "passive"))
      (node (ref "R14") (pin "2") (pinfunction "2_2") (pintype "passive"))
      (node (ref "R78") (pin "1") (pinfunction "1_1") (pintype "passive"))
    )
    (net (code "57") (name "Net-(R41-Pad1)") (class "Default")
      (node (ref "R41") (pin "1") (pinfunction "1_1") (pintype "passive"))
      (node (ref "R42") (pin "2") (pinfunction "2_2") (pintype "passive"))
    )
    (net (code "58") (name "Net-(RP1-R1-1)") (class "Default")
      (node (ref "RP1") (pin "1") (pinfunction "R1-1_1") (pintype "passive"))
      (node (ref "U7") (pin "24") (pinfunction "PA8/TIM1_CH1_24") (pintype "bidirectional"))
    )
    (net (code "59") (name "Net-(RP1-R2-1)") (class "Default")
      (node (ref "RP1") (pin "2") (pinfunction "R2-1_2") (pintype "passive"))
      (node (ref "U7") (pin "23") (pinfunction "PB15/OP1P0/TIM1_CH3N_23") (pintype "bidirectional"))
    )
    (net (code "60") (name "Net-(RP1-R3-1)") (class "Default")
      (node (ref "RP1") (pin "3") (pinfunction "R3-1_3") (pintype "passive"))
      (node (ref "U7") (pin "22") (pinfunction "PB14/OP2P0/TIM1_CH2N_22") (pintype "bidirectional"))
    )
    (net (code "61") (name "Net-(RP1-R4-1)") (class "Default")
      (node (ref "RP1") (pin "4") (pinfunction "R4-1_4") (pintype "passive"))
      (node (ref "U7") (pin "21") (pinfunction "PB13/TIM1_CH1N_21") (pintype "bidirectional"))
    )
    (net (code "62") (name "Net-(U7-PA9{slash}TIM1_CH2)") (class "Default")
      (node (ref "R20") (pin "2") (pinfunction "2_2") (pintype "passive"))
      (node (ref "U7") (pin "25") (pinfunction "PA9/TIM1_CH2_25") (pintype "bidirectional"))
    )
    (net (code "63") (name "Net-(U7-PA10{slash}TIM1_CH3)") (class "Default")
      (node (ref "R19") (pin "2") (pinfunction "2_2") (pintype "passive"))
      (node (ref "U7") (pin "26") (pinfunction "PA10/TIM1_CH3_26") (pintype "bidirectional"))
    )
    (net (code "64") (name "V3.3") (class "Default")
      (node (ref "C22") (pin "1") (pinfunction "1_1") (pintype "passive"))
      (node (ref "C28") (pin "1") (pinfunction "1_1") (pintype "passive"))
      (node (ref "C60") (pin "1") (pinfunction "1_1") (pintype "passive"))
      (node (ref "P1") (pin "2") (pintype "passive"))
      (node (ref "R47") (pin "1") (pinfunction "1_1") (pintype "passive"))
      (node (ref "R54") (pin "1") (pinfunction "1_1") (pintype "passive"))
      (node (ref "R57") (pin "1") (pinfunction "1_1") (pintype "passive"))
      (node (ref "U7") (pin "6") (pinfunction "VDD_6") (pintype "power_in"))
      (node (ref "U7") (pin "8") (pinfunction "NRST_8") (pintype "input"))
    )
    (net (code "65") (name "V310") (class "Default")
      (node (ref "C71") (pin "1") (pinfunction "1_1") (pintype "passive"))
      (node (ref "Q1") (pin "2") (pinfunction "D_2") (pintype "passive"))
      (node (ref "Q3") (pin "2") (pinfunction "D_2") (pintype "passive"))
      (node (ref "Q5") (pin "2") (pinfunction "D_2") (pintype "passive"))
      (node (ref "R41") (pin "2") (pinfunction "2_2") (pintype "passive"))
    )
  )
)
